# LedKeychainATtiny2313.net
KiCad netlist of a schematic drawn in EasyEDA Pro
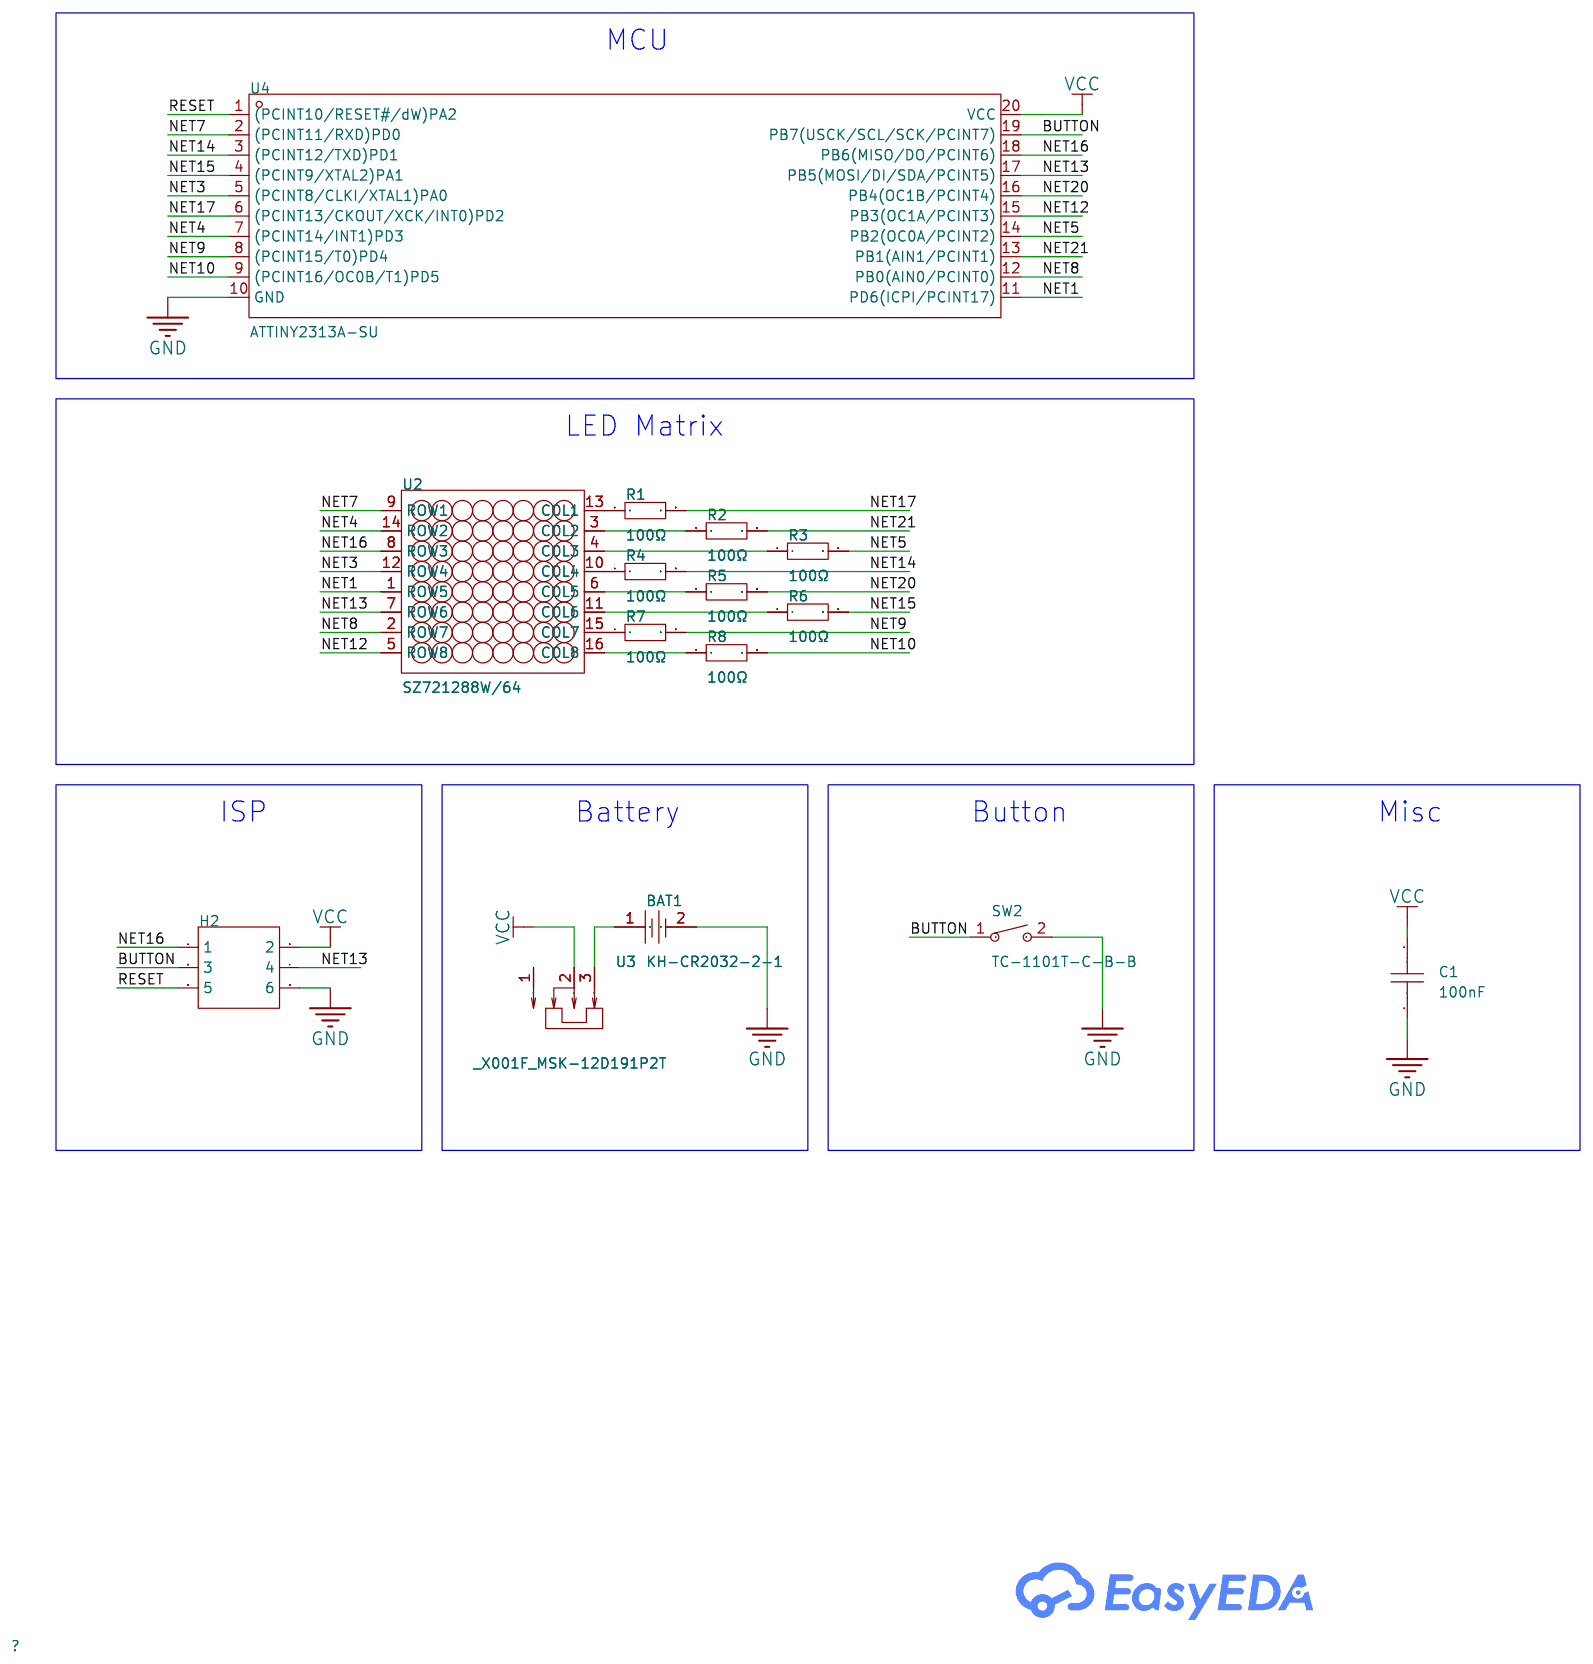
[diagram p0: schematic sheet]

(export (version "E")
  (design (tool "Eeschema 10.0.6"))
  (components
    (comp (ref "BAT1")
      (value "KH-CR2032-2-1")
      (footprint "easyedapro:BAT-TH_KH-CR2032-2-1")
      (fields (field (name "Manufacturer") "kinghelm(金航标)"))
      (libsource (lib "easyedapro") (part "KH-CR2032-2-1"))
    )
    (comp (ref "C1")
      (value "100nF")
      (footprint "easyedapro:C0805")
      (libsource (lib "easyedapro") (part "CAP"))
    )
    (comp (ref "H2")
      (value "~")
      (footprint "easyedapro:HDR-TH_6P-P2.54-V-R2-C3-S2.54_A2541WV-2X3P")
      (libsource (lib "easyedapro") (part "HDR-M-2.54_2x3"))
    )
    (comp (ref "R1")
      (value "100Ω")
      (footprint "easyedapro:R0805")
      (fields
        (field (name "Manufacturer Part") "0805W8F1002T5E")
        (field (name "Manufacturer") "UNI-ROYAL(厚声)")
      )
      (libsource (lib "easyedapro") (part "0805W8F1002T5E"))
    )
    (comp (ref "R2")
      (value "100Ω")
      (footprint "easyedapro:R0805")
      (fields
        (field (name "Manufacturer Part") "0805W8F1002T5E")
        (field (name "Manufacturer") "UNI-ROYAL(厚声)")
      )
      (libsource (lib "easyedapro") (part "0805W8F1002T5E"))
    )
    (comp (ref "R3")
      (value "100Ω")
      (footprint "easyedapro:R0805")
      (fields
        (field (name "Manufacturer Part") "0805W8F1002T5E")
        (field (name "Manufacturer") "UNI-ROYAL(厚声)")
      )
      (libsource (lib "easyedapro") (part "0805W8F1002T5E"))
    )
    (comp (ref "R4")
      (value "100Ω")
      (footprint "easyedapro:R0805")
      (fields
        (field (name "Manufacturer Part") "0805W8F1002T5E")
        (field (name "Manufacturer") "UNI-ROYAL(厚声)")
      )
      (libsource (lib "easyedapro") (part "0805W8F1002T5E"))
    )
    (comp (ref "R5")
      (value "100Ω")
      (footprint "easyedapro:R0805")
      (fields
        (field (name "Manufacturer Part") "0805W8F1002T5E")
        (field (name "Manufacturer") "UNI-ROYAL(厚声)")
      )
      (libsource (lib "easyedapro") (part "0805W8F1002T5E"))
    )
    (comp (ref "R6")
      (value "100Ω")
      (footprint "easyedapro:R0805")
      (fields
        (field (name "Manufacturer Part") "0805W8F1002T5E")
        (field (name "Manufacturer") "UNI-ROYAL(厚声)")
      )
      (libsource (lib "easyedapro") (part "0805W8F1002T5E"))
    )
    (comp (ref "R7")
      (value "100Ω")
      (footprint "easyedapro:R0805")
      (fields
        (field (name "Manufacturer Part") "0805W8F1002T5E")
        (field (name "Manufacturer") "UNI-ROYAL(厚声)")
      )
      (libsource (lib "easyedapro") (part "0805W8F1002T5E"))
    )
    (comp (ref "R8")
      (value "100Ω")
      (footprint "easyedapro:R0805")
      (fields
        (field (name "Manufacturer Part") "0805W8F1002T5E")
        (field (name "Manufacturer") "UNI-ROYAL(厚声)")
      )
      (libsource (lib "easyedapro") (part "0805W8F1002T5E"))
    )
    (comp (ref "SW2")
      (value "TC-1101T-C-B-B")
      (footprint "easyedapro:KEY-TH_2P-L6.0-W3.5-P6.50")
      (fields (field (name "Manufacturer") "XKB Connectivity(中国星坤)"))
      (libsource (lib "easyedapro") (part "TC-1101T-C-B-B"))
    )
    (comp (ref "U2")
      (value "SZ721288W/64")
      (footprint "easyedapro:LED-SEG-TH_SZ421288N-64")
      (description "Dot Matrix Number:8x8 Emitting Color:White Polarity:Common Cathode")
      (fields (field (name "Manufacturer") "ARKLED(方舟)"))
      (libsource (lib "easyedapro") (part "SZ721288W/64"))
    )
    (comp (ref "U3")
      (value "_X001F_MSK-12D191P2T")
      (footprint "easyedapro:SW-TH_MSK-12D191P2T")
      (fields (field (name "Manufacturer Part") "_x001F_MSK-12D191P2T"))
      (libsource (lib "easyedapro") (part "MSK-12D19"))
    )
    (comp (ref "U4")
      (value "ATTINY2313A-SU")
      (footprint "easyedapro:SOIC-20_L13.0-W7.6-P1.27-LS10.3-BL")
      (fields (field (name "Manufacturer") "MICROCHIP(美国微芯)"))
      (libsource (lib "easyedapro") (part "ATTINY2313A-SU_C424094"))
    )
  )
  (nets
    (net (code "1") (name "/BUTTON") (class "Default")
      (node (ref "H2") (pin "3") (pinfunction "3_3") (pintype "input"))
      (node (ref "SW2") (pin "1") (pinfunction "1_1") (pintype "input"))
      (node (ref "U4") (pin "19") (pinfunction "PB7(USCK/SCL/SCK/PCINT7)_19") (pintype "unspecified"))
    )
    (net (code "2") (name "/NET1") (class "Default")
      (node (ref "U2") (pin "1") (pinfunction "ROW5_1") (pintype "unspecified"))
      (node (ref "U4") (pin "11") (pinfunction "PD6(ICPI/PCINT17)_11") (pintype "unspecified"))
    )
    (net (code "3") (name "/NET3") (class "Default")
      (node (ref "U2") (pin "12") (pinfunction "ROW4_12") (pintype "unspecified"))
      (node (ref "U4") (pin "5") (pinfunction "(PCINT8/CLKI/XTAL1)PA0_5") (pintype "unspecified"))
    )
    (net (code "4") (name "/NET4") (class "Default")
      (node (ref "U2") (pin "14") (pinfunction "ROW2_14") (pintype "unspecified"))
      (node (ref "U4") (pin "7") (pinfunction "(PCINT14/INT1)PD3_7") (pintype "unspecified"))
    )
    (net (code "5") (name "/NET5") (class "Default")
      (node (ref "R3") (pin "2") (pinfunction "2_2") (pintype "input"))
      (node (ref "U4") (pin "14") (pinfunction "PB2(OC0A/PCINT2)_14") (pintype "unspecified"))
    )
    (net (code "6") (name "/NET7") (class "Default")
      (node (ref "U2") (pin "9") (pinfunction "ROW1_9") (pintype "unspecified"))
      (node (ref "U4") (pin "2") (pinfunction "(PCINT11/RXD)PD0_2") (pintype "unspecified"))
    )
    (net (code "7") (name "/NET8") (class "Default")
      (node (ref "U2") (pin "2") (pinfunction "ROW7_2") (pintype "unspecified"))
      (node (ref "U4") (pin "12") (pinfunction "PB0(AIN0/PCINT0)_12") (pintype "unspecified"))
    )
    (net (code "8") (name "/NET9") (class "Default")
      (node (ref "R7") (pin "2") (pinfunction "2_2") (pintype "input"))
      (node (ref "U4") (pin "8") (pinfunction "(PCINT15/T0)PD4_8") (pintype "unspecified"))
    )
    (net (code "9") (name "/NET10") (class "Default")
      (node (ref "R8") (pin "2") (pinfunction "2_2") (pintype "input"))
      (node (ref "U4") (pin "9") (pinfunction "(PCINT16/OC0B/T1)PD5_9") (pintype "unspecified"))
    )
    (net (code "10") (name "/NET12") (class "Default")
      (node (ref "U2") (pin "5") (pinfunction "ROW8_5") (pintype "unspecified"))
      (node (ref "U4") (pin "15") (pinfunction "PB3(OC1A/PCINT3)_15") (pintype "unspecified"))
    )
    (net (code "11") (name "/NET13") (class "Default")
      (node (ref "H2") (pin "4") (pinfunction "4_4") (pintype "input"))
      (node (ref "U2") (pin "7") (pinfunction "ROW6_7") (pintype "unspecified"))
      (node (ref "U4") (pin "17") (pinfunction "PB5(MOSI/DI/SDA/PCINT5)_17") (pintype "unspecified"))
    )
    (net (code "12") (name "/NET14") (class "Default")
      (node (ref "R4") (pin "2") (pinfunction "2_2") (pintype "input"))
      (node (ref "U4") (pin "3") (pinfunction "(PCINT12/TXD)PD1_3") (pintype "unspecified"))
    )
    (net (code "13") (name "/NET15") (class "Default")
      (node (ref "R6") (pin "2") (pinfunction "2_2") (pintype "input"))
      (node (ref "U4") (pin "4") (pinfunction "(PCINT9/XTAL2)PA1_4") (pintype "unspecified"))
    )
    (net (code "14") (name "/NET16") (class "Default")
      (node (ref "H2") (pin "1") (pinfunction "1_1") (pintype "input"))
      (node (ref "U2") (pin "8") (pinfunction "ROW3_8") (pintype "unspecified"))
      (node (ref "U4") (pin "18") (pinfunction "PB6(MISO/DO/PCINT6)_18") (pintype "unspecified"))
    )
    (net (code "15") (name "/NET17") (class "Default")
      (node (ref "R1") (pin "2") (pinfunction "2_2") (pintype "input"))
      (node (ref "U4") (pin "6") (pinfunction "(PCINT13/CKOUT/XCK/INT0)PD2_6") (pintype "unspecified"))
    )
    (net (code "16") (name "/NET20") (class "Default")
      (node (ref "R5") (pin "2") (pinfunction "2_2") (pintype "input"))
      (node (ref "U4") (pin "16") (pinfunction "PB4(OC1B/PCINT4)_16") (pintype "unspecified"))
    )
    (net (code "17") (name "/NET21") (class "Default")
      (node (ref "R2") (pin "2") (pinfunction "2_2") (pintype "input"))
      (node (ref "U4") (pin "13") (pinfunction "PB1(AIN1/PCINT1)_13") (pintype "unspecified"))
    )
    (net (code "18") (name "/RESET") (class "Default")
      (node (ref "H2") (pin "5") (pinfunction "5_5") (pintype "input"))
      (node (ref "U4") (pin "1") (pinfunction "(PCINT10/RESET#/dW)PA2_1") (pintype "unspecified"))
    )
    (net (code "19") (name "GND") (class "Default")
      (node (ref "BAT1") (pin "2") (pinfunction "2_2") (pintype "input"))
      (node (ref "C1") (pin "1") (pinfunction "1_1") (pintype "input"))
      (node (ref "H2") (pin "6") (pinfunction "6_6") (pintype "input"))
      (node (ref "SW2") (pin "2") (pinfunction "2_2") (pintype "input"))
      (node (ref "U4") (pin "10") (pinfunction "GND_10") (pintype "unspecified"))
    )
    (net (code "20") (name "Net-(BAT1-Pad1)") (class "Default")
      (node (ref "BAT1") (pin "1") (pinfunction "1_1") (pintype "input"))
      (node (ref "U3") (pin "3") (pinfunction "3_3") (pintype "unspecified"))
    )
    (net (code "21") (name "Net-(U2-COL1)") (class "Default")
      (node (ref "R1") (pin "1") (pinfunction "1_1") (pintype "input"))
      (node (ref "U2") (pin "13") (pinfunction "COL1_13") (pintype "unspecified"))
    )
    (net (code "22") (name "Net-(U2-COL2)") (class "Default")
      (node (ref "R2") (pin "1") (pinfunction "1_1") (pintype "input"))
      (node (ref "U2") (pin "3") (pinfunction "COL2_3") (pintype "unspecified"))
    )
    (net (code "23") (name "Net-(U2-COL3)") (class "Default")
      (node (ref "R3") (pin "1") (pinfunction "1_1") (pintype "input"))
      (node (ref "U2") (pin "4") (pinfunction "COL3_4") (pintype "unspecified"))
    )
    (net (code "24") (name "Net-(U2-COL4)") (class "Default")
      (node (ref "R4") (pin "1") (pinfunction "1_1") (pintype "input"))
      (node (ref "U2") (pin "10") (pinfunction "COL4_10") (pintype "unspecified"))
    )
    (net (code "25") (name "Net-(U2-COL5)") (class "Default")
      (node (ref "R5") (pin "1") (pinfunction "1_1") (pintype "input"))
      (node (ref "U2") (pin "6") (pinfunction "COL5_6") (pintype "unspecified"))
    )
    (net (code "26") (name "Net-(U2-COL6)") (class "Default")
      (node (ref "R6") (pin "1") (pinfunction "1_1") (pintype "input"))
      (node (ref "U2") (pin "11") (pinfunction "COL6_11") (pintype "unspecified"))
    )
    (net (code "27") (name "Net-(U2-COL7)") (class "Default")
      (node (ref "R7") (pin "1") (pinfunction "1_1") (pintype "input"))
      (node (ref "U2") (pin "15") (pinfunction "COL7_15") (pintype "unspecified"))
    )
    (net (code "28") (name "Net-(U2-COL8)") (class "Default")
      (node (ref "R8") (pin "1") (pinfunction "1_1") (pintype "input"))
      (node (ref "U2") (pin "16") (pinfunction "COL8_16") (pintype "unspecified"))
    )
    (net (code "29") (name "VCC") (class "Default")
      (node (ref "C1") (pin "2") (pinfunction "2_2") (pintype "input"))
      (node (ref "H2") (pin "2") (pinfunction "2_2") (pintype "input"))
      (node (ref "U3") (pin "2") (pinfunction "2_2") (pintype "unspecified"))
      (node (ref "U4") (pin "20") (pinfunction "VCC_20") (pintype "unspecified"))
    )
    (net (code "30") (name "unconnected-(U3-Pad1)") (class "Default")
      (node (ref "U3") (pin "1") (pinfunction "1_1") (pintype "unspecified"))
    )
  )
)
